# Controle.net
KiCad netlist of a schematic drawn in EAGLE
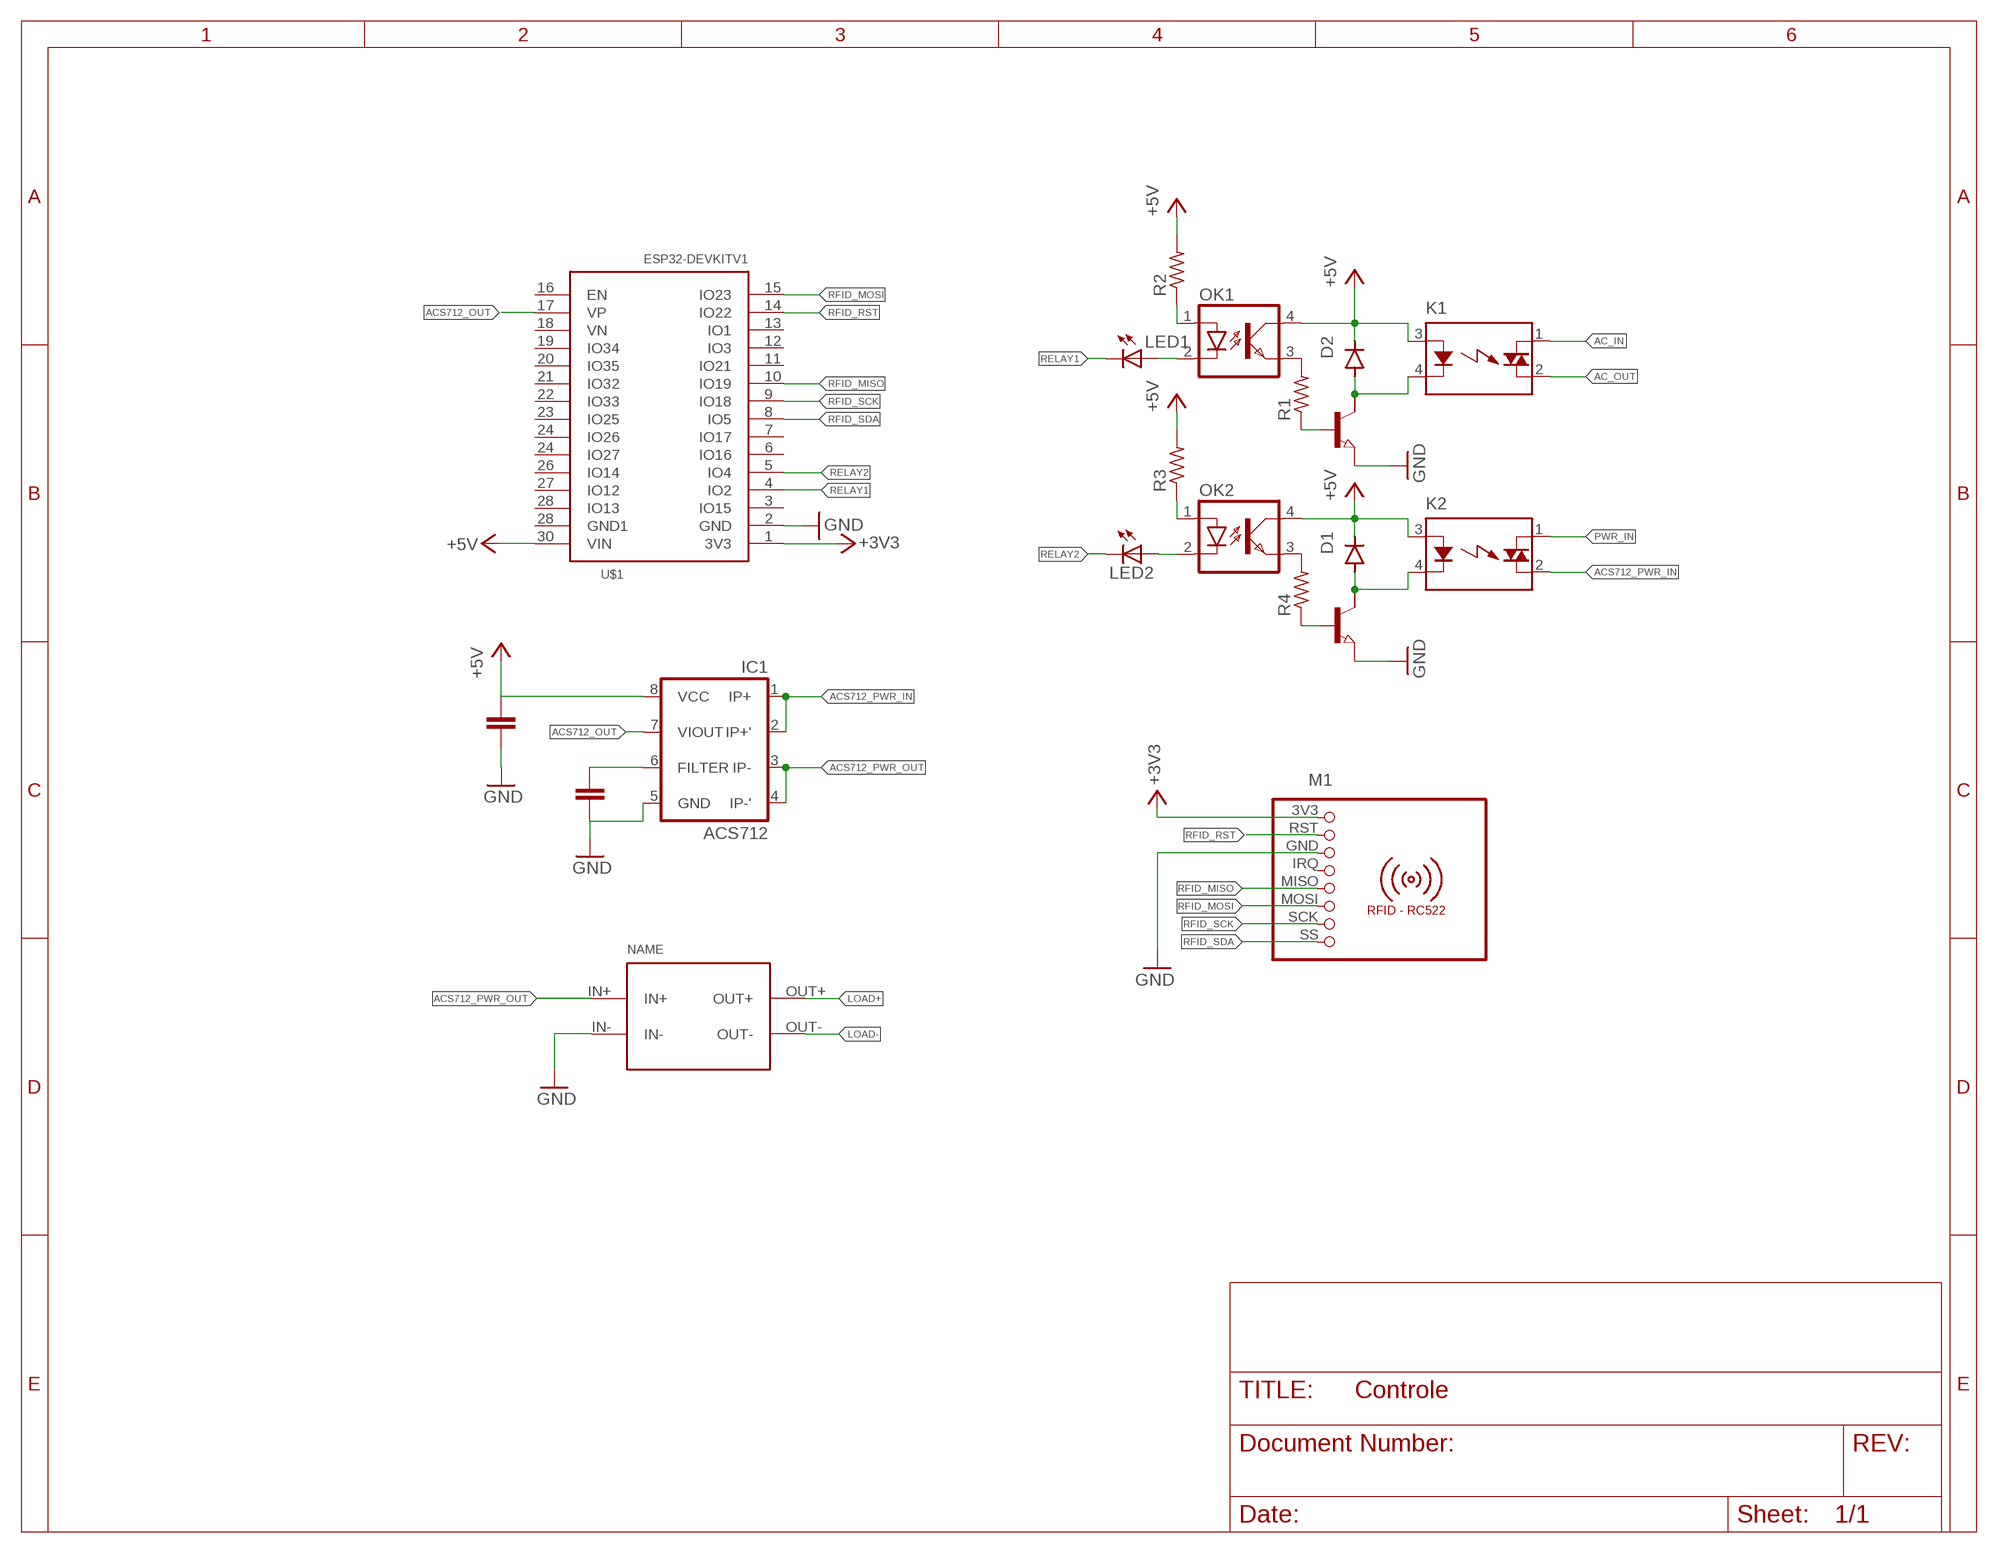
[diagram p0: schematic, sheet 1]

(export (version "E")
  (design (tool "Eeschema 10.0.6"))
  (components
    (comp (ref "D1")
      (value "1N4004")
      (footprint "eagle-import:DO41-10")
      (libsource (lib "eagle-import") (part "1N4004"))
    )
    (comp (ref "D2")
      (value "1N4004")
      (footprint "eagle-import:DO41-10")
      (libsource (lib "eagle-import") (part "1N4004"))
    )
    (comp (ref "IC1")
      (value "ACS712")
      (footprint "eagle-import:SO08")
      (libsource (lib "eagle-import") (part "ACS712"))
    )
    (comp (ref "K1")
      (value "AQ2A2-J-ZP3")
      (footprint "eagle-import:AQ1-FLAT")
      (fields (field (name "MPN") "AQ2A2-ZP3/28VDC"))
      (libsource (lib "eagle-import") (part "AQ?2A2-J-ZP3"))
    )
    (comp (ref "K2")
      (value "AQ2A2-J-ZP3")
      (footprint "eagle-import:AQ1-FLAT")
      (fields (field (name "MPN") "AQ2A2-ZP3/28VDC"))
      (libsource (lib "eagle-import") (part "AQ?2A2-J-ZP3"))
    )
    (comp (ref "LED1")
      (value "LED")
      (footprint "eagle-import:SMARTLED-TTW")
      (libsource (lib "eagle-import") (part "LED"))
    )
    (comp (ref "LED2")
      (value "LED")
      (footprint "eagle-import:SMARTLED-TTW")
      (libsource (lib "eagle-import") (part "LED"))
    )
    (comp (ref "M1")
      (value "RFID-RC522")
      (footprint "eagle-import:RFID-RC522")
      (libsource (lib "eagle-import") (part "RFID-RC522"))
    )
    (comp (ref "OK1")
      (value "SFH618A-3X006")
      (footprint "eagle-import:DIP4-400")
      (libsource (lib "eagle-import") (part "SFH618?A-3X006"))
    )
    (comp (ref "OK2")
      (value "SFH618A-3X006")
      (footprint "eagle-import:DIP4-400")
      (libsource (lib "eagle-import") (part "SFH618?A-3X006"))
    )
    (comp (ref "Q1")
      (value "NPN-TRANSISTIOR-2COLSOT89")
      (footprint "eagle-import:SOT89")
      (libsource (lib "eagle-import") (part "NPN-TRANSISTIOR-2COLSOT89"))
    )
    (comp (ref "Q2")
      (value "NPN-TRANSISTIOR-2COLSOT89")
      (footprint "eagle-import:SOT89")
      (libsource (lib "eagle-import") (part "NPN-TRANSISTIOR-2COLSOT89"))
    )
    (comp (ref "R1")
      (value "R-US_M0805")
      (footprint "eagle-import:M0805")
      (libsource (lib "eagle-import") (part "R-US_M0805"))
    )
    (comp (ref "R2")
      (value "R-US_M0805")
      (footprint "eagle-import:M0805")
      (libsource (lib "eagle-import") (part "R-US_M0805"))
    )
    (comp (ref "R3")
      (value "R-US_M0805")
      (footprint "eagle-import:M0805")
      (libsource (lib "eagle-import") (part "R-US_M0805"))
    )
    (comp (ref "R4")
      (value "R-US_M0805")
      (footprint "eagle-import:M0805")
      (libsource (lib "eagle-import") (part "R-US_M0805"))
    )
    (comp (ref "U$1")
      (value "ESP32DEVKITV1")
      (footprint "eagle-import:ESP32-DEVKITV1")
      (libsource (lib "eagle-import") (part "ESP32DEVKITV1"))
    )
    (comp (ref "U$2")
      (value "CONVERSOR_DC/DC")
      (footprint "eagle-import:CP8-ADJ")
      (libsource (lib "eagle-import") (part "CONVERSOR_DC/DC"))
    )
  )
  (nets
    (net (code "1") (name "+3V3") (class "Default")
      (node (ref "M1") (pin "3V3") (pinfunction "1_3V3") (pintype "passive"))
      (node (ref "U$1") (pin "1") (pinfunction "3V3_1") (pintype "bidirectional"))
    )
    (net (code "2") (name "+5V") (class "Default")
      (node (ref "D1") (pin "C") (pinfunction "C_C") (pintype "passive"))
      (node (ref "D2") (pin "C") (pinfunction "C_C") (pintype "passive"))
      (node (ref "IC1") (pin "8") (pinfunction "VCC_8") (pintype "power_in"))
      (node (ref "K1") (pin "3") (pinfunction "A_3") (pintype "passive"))
      (node (ref "K2") (pin "3") (pinfunction "A_3") (pintype "passive"))
      (node (ref "OK1") (pin "4") (pinfunction "COL_4") (pintype "passive"))
      (node (ref "OK2") (pin "4") (pinfunction "COL_4") (pintype "passive"))
      (node (ref "R2") (pin "2") (pinfunction "2_2") (pintype "passive"))
      (node (ref "R3") (pin "2") (pinfunction "2_2") (pintype "passive"))
      (node (ref "U$1") (pin "30") (pinfunction "VIN_30") (pintype "bidirectional"))
    )
    (net (code "3") (name "ACS712_OUT") (class "Default")
      (node (ref "IC1") (pin "7") (pinfunction "VIOUT_7") (pintype "output"))
      (node (ref "U$1") (pin "17") (pinfunction "VP_17") (pintype "bidirectional"))
    )
    (net (code "4") (name "ACS712_PWR_IN") (class "Default")
      (node (ref "IC1") (pin "1") (pinfunction "IP+_1") (pintype "output"))
      (node (ref "IC1") (pin "2") (pinfunction "IP+'_2") (pintype "output"))
      (node (ref "K2") (pin "2") (pinfunction "DS2_2") (pintype "passive"))
    )
    (net (code "5") (name "ACS712_PWR_OUT") (class "Default")
      (node (ref "IC1") (pin "3") (pinfunction "IP-_3") (pintype "input"))
      (node (ref "IC1") (pin "4") (pinfunction "IP-'_4") (pintype "input"))
      (node (ref "U$2") (pin "IN+") (pinfunction "IN+_IN+") (pintype "passive"))
    )
    (net (code "6") (name "AC_IN") (class "Default")
      (node (ref "K1") (pin "1") (pinfunction "DS1_1") (pintype "passive"))
    )
    (net (code "7") (name "AC_OUT") (class "Default")
      (node (ref "K1") (pin "2") (pinfunction "DS2_2") (pintype "passive"))
    )
    (net (code "8") (name "GND") (class "Default")
      (node (ref "IC1") (pin "5") (pinfunction "GND_5") (pintype "input"))
      (node (ref "M1") (pin "GND") (pinfunction "3_GND") (pintype "passive"))
      (node (ref "Q1") (pin "3") (pinfunction "E_3") (pintype "passive"))
      (node (ref "Q2") (pin "3") (pinfunction "E_3") (pintype "passive"))
      (node (ref "U$1") (pin "2") (pinfunction "GND_2") (pintype "bidirectional"))
      (node (ref "U$2") (pin "IN-") (pinfunction "IN-_IN-") (pintype "passive"))
    )
    (net (code "9") (name "LOAD+") (class "Default")
      (node (ref "U$2") (pin "OUT+") (pinfunction "OUT+_OUT+") (pintype "passive"))
    )
    (net (code "10") (name "LOAD-") (class "Default")
      (node (ref "U$2") (pin "OUT-") (pinfunction "OUT-_OUT-") (pintype "passive"))
    )
    (net (code "11") (name "Net-(K1-K)") (class "Default")
      (node (ref "D2") (pin "A") (pinfunction "A_A") (pintype "passive"))
      (node (ref "K1") (pin "4") (pinfunction "K_4") (pintype "passive"))
      (node (ref "Q2") (pin "2") (pinfunction "C_2") (pintype "passive"))
    )
    (net (code "12") (name "Net-(K2-K)") (class "Default")
      (node (ref "D1") (pin "A") (pinfunction "A_A") (pintype "passive"))
      (node (ref "K2") (pin "4") (pinfunction "K_4") (pintype "passive"))
      (node (ref "Q1") (pin "2") (pinfunction "C_2") (pintype "passive"))
    )
    (net (code "13") (name "Net-(LED1-A)") (class "Default")
      (node (ref "LED1") (pin "A@1") (pinfunction "A_A@1") (pintype "passive"))
      (node (ref "OK1") (pin "2") (pinfunction "C_2") (pintype "passive"))
    )
    (net (code "14") (name "Net-(LED2-A)") (class "Default")
      (node (ref "LED2") (pin "A@1") (pinfunction "A_A@1") (pintype "passive"))
      (node (ref "OK2") (pin "2") (pinfunction "C_2") (pintype "passive"))
    )
    (net (code "15") (name "Net-(OK1-A)") (class "Default")
      (node (ref "OK1") (pin "1") (pinfunction "A_1") (pintype "passive"))
      (node (ref "R2") (pin "1") (pinfunction "1_1") (pintype "passive"))
    )
    (net (code "16") (name "Net-(OK1-EMIT)") (class "Default")
      (node (ref "OK1") (pin "3") (pinfunction "EMIT_3") (pintype "passive"))
      (node (ref "R1") (pin "2") (pinfunction "2_2") (pintype "passive"))
    )
    (net (code "17") (name "Net-(OK2-A)") (class "Default")
      (node (ref "OK2") (pin "1") (pinfunction "A_1") (pintype "passive"))
      (node (ref "R3") (pin "1") (pinfunction "1_1") (pintype "passive"))
    )
    (net (code "18") (name "Net-(OK2-EMIT)") (class "Default")
      (node (ref "OK2") (pin "3") (pinfunction "EMIT_3") (pintype "passive"))
      (node (ref "R4") (pin "2") (pinfunction "2_2") (pintype "passive"))
    )
    (net (code "19") (name "Net-(Q1-B)") (class "Default")
      (node (ref "Q1") (pin "1") (pinfunction "B_1") (pintype "passive"))
      (node (ref "R4") (pin "1") (pinfunction "1_1") (pintype "passive"))
    )
    (net (code "20") (name "Net-(Q2-B)") (class "Default")
      (node (ref "Q2") (pin "1") (pinfunction "B_1") (pintype "passive"))
      (node (ref "R1") (pin "1") (pinfunction "1_1") (pintype "passive"))
    )
    (net (code "21") (name "PWR_IN") (class "Default")
      (node (ref "K2") (pin "1") (pinfunction "DS1_1") (pintype "passive"))
    )
    (net (code "22") (name "RELAY1") (class "Default")
      (node (ref "LED1") (pin "C@1") (pinfunction "C_C@1") (pintype "passive"))
      (node (ref "U$1") (pin "4") (pinfunction "IO2_4") (pintype "bidirectional"))
    )
    (net (code "23") (name "RELAY2") (class "Default")
      (node (ref "LED2") (pin "C@1") (pinfunction "C_C@1") (pintype "passive"))
      (node (ref "U$1") (pin "5") (pinfunction "IO4_5") (pintype "bidirectional"))
    )
    (net (code "24") (name "RFID_MISO") (class "Default")
      (node (ref "M1") (pin "MISO") (pinfunction "5_MISO") (pintype "passive"))
      (node (ref "U$1") (pin "10") (pinfunction "IO19_10") (pintype "bidirectional"))
    )
    (net (code "25") (name "RFID_MOSI") (class "Default")
      (node (ref "M1") (pin "MOSI") (pinfunction "6_MOSI") (pintype "passive"))
      (node (ref "U$1") (pin "15") (pinfunction "IO23_15") (pintype "bidirectional"))
    )
    (net (code "26") (name "RFID_RST") (class "Default")
      (node (ref "M1") (pin "RST") (pinfunction "2_RST") (pintype "passive"))
      (node (ref "U$1") (pin "14") (pinfunction "IO22_14") (pintype "bidirectional"))
    )
    (net (code "27") (name "RFID_SCK") (class "Default")
      (node (ref "M1") (pin "SCK") (pinfunction "7_SCK") (pintype "passive"))
      (node (ref "U$1") (pin "9") (pinfunction "IO18_9") (pintype "bidirectional"))
    )
    (net (code "28") (name "RFID_SDA") (class "Default")
      (node (ref "M1") (pin "SS") (pinfunction "8_SS") (pintype "passive"))
      (node (ref "U$1") (pin "8") (pinfunction "IO5_8") (pintype "bidirectional"))
    )
    (net (code "29") (name "unconnected-(IC1-FILTER-Pad6)") (class "Default")
      (node (ref "IC1") (pin "6") (pinfunction "FILTER_6") (pintype "input"))
    )
    (net (code "30") (name "unconnected-(M1-4-PadIRQ)") (class "Default")
      (node (ref "M1") (pin "IRQ") (pinfunction "4_IRQ") (pintype "passive"))
    )
    (net (code "31") (name "unconnected-(Q1-C{slash}-Pad2@1)") (class "Default")
      (node (ref "Q1") (pin "2@1") (pinfunction "C/_2@1") (pintype "passive"))
    )
    (net (code "32") (name "unconnected-(Q2-C{slash}-Pad2@1)") (class "Default")
      (node (ref "Q2") (pin "2@1") (pinfunction "C/_2@1") (pintype "passive"))
    )
    (net (code "33") (name "unconnected-(U$1-EN-Pad16)") (class "Default")
      (node (ref "U$1") (pin "16") (pinfunction "EN_16") (pintype "bidirectional"))
    )
    (net (code "34") (name "unconnected-(U$1-GND1-Pad28)") (class "Default")
      (node (ref "U$1") (pin "28") (pinfunction "GND1_28") (pintype "bidirectional"))
    )
    (net (code "35") (name "unconnected-(U$1-IO1-Pad13)") (class "Default")
      (node (ref "U$1") (pin "13") (pinfunction "IO1_13") (pintype "bidirectional"))
    )
    (net (code "36") (name "unconnected-(U$1-IO3-Pad12)") (class "Default")
      (node (ref "U$1") (pin "12") (pinfunction "IO3_12") (pintype "bidirectional"))
    )
    (net (code "37") (name "unconnected-(U$1-IO12-Pad27)") (class "Default")
      (node (ref "U$1") (pin "27") (pinfunction "IO12_27") (pintype "bidirectional"))
    )
    (net (code "38") (name "unconnected-(U$1-IO13-Pad28)") (class "Default")
      (node (ref "U$1") (pin "28") (pinfunction "IO13_28") (pintype "bidirectional"))
    )
    (net (code "39") (name "unconnected-(U$1-IO14-Pad26)") (class "Default")
      (node (ref "U$1") (pin "26") (pinfunction "IO14_26") (pintype "bidirectional"))
    )
    (net (code "40") (name "unconnected-(U$1-IO15-Pad3)") (class "Default")
      (node (ref "U$1") (pin "3") (pinfunction "IO15_3") (pintype "bidirectional"))
    )
    (net (code "41") (name "unconnected-(U$1-IO16-Pad6)") (class "Default")
      (node (ref "U$1") (pin "6") (pinfunction "IO16_6") (pintype "bidirectional"))
    )
    (net (code "42") (name "unconnected-(U$1-IO17-Pad7)") (class "Default")
      (node (ref "U$1") (pin "7") (pinfunction "IO17_7") (pintype "bidirectional"))
    )
    (net (code "43") (name "unconnected-(U$1-IO21-Pad11)") (class "Default")
      (node (ref "U$1") (pin "11") (pinfunction "IO21_11") (pintype "bidirectional"))
    )
    (net (code "44") (name "unconnected-(U$1-IO25-Pad23)") (class "Default")
      (node (ref "U$1") (pin "23") (pinfunction "IO25_23") (pintype "bidirectional"))
    )
    (net (code "45") (name "unconnected-(U$1-IO26-Pad24)") (class "Default")
      (node (ref "U$1") (pin "24") (pinfunction "IO26_24") (pintype "bidirectional"))
    )
    (net (code "46") (name "unconnected-(U$1-IO27-Pad24)") (class "Default")
      (node (ref "U$1") (pin "24") (pinfunction "IO27_24") (pintype "bidirectional"))
    )
    (net (code "47") (name "unconnected-(U$1-IO32-Pad21)") (class "Default")
      (node (ref "U$1") (pin "21") (pinfunction "IO32_21") (pintype "bidirectional"))
    )
    (net (code "48") (name "unconnected-(U$1-IO33-Pad22)") (class "Default")
      (node (ref "U$1") (pin "22") (pinfunction "IO33_22") (pintype "bidirectional"))
    )
    (net (code "49") (name "unconnected-(U$1-IO34-Pad19)") (class "Default")
      (node (ref "U$1") (pin "19") (pinfunction "IO34_19") (pintype "bidirectional"))
    )
    (net (code "50") (name "unconnected-(U$1-IO35-Pad20)") (class "Default")
      (node (ref "U$1") (pin "20") (pinfunction "IO35_20") (pintype "bidirectional"))
    )
    (net (code "51") (name "unconnected-(U$1-VN-Pad18)") (class "Default")
      (node (ref "U$1") (pin "18") (pinfunction "VN_18") (pintype "bidirectional"))
    )
  )
)
